# poe.net
KiCad netlist of a schematic drawn in EAGLE
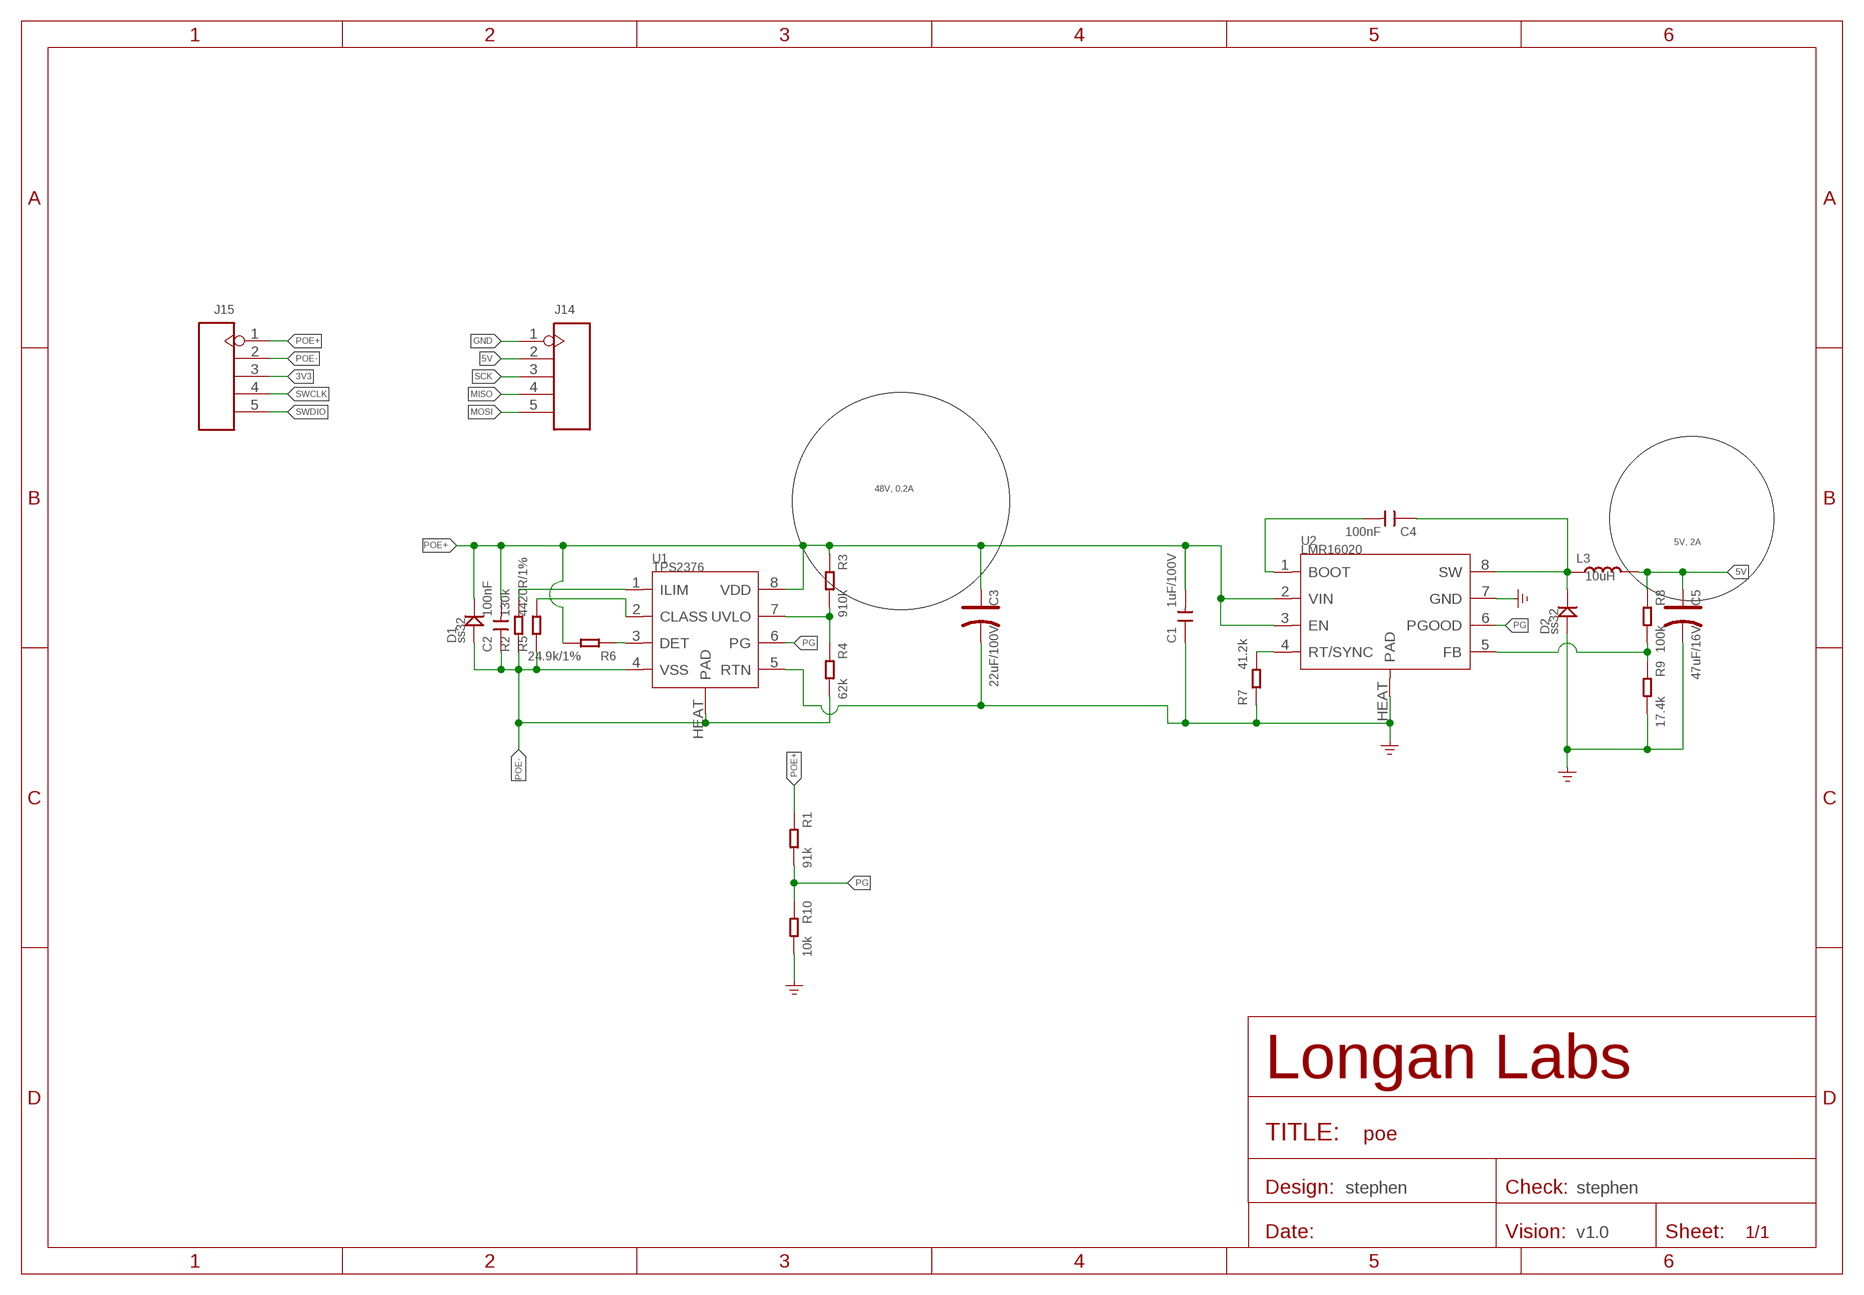
[diagram p0: schematic, sheet 1]

(export (version "E")
  (design (tool "Eeschema 10.0.6"))
  (components
    (comp (ref "C1")
      (value "1uF/100V")
      (footprint "eagle-import:C0805")
      (libsource (lib "eagle-import") (part "CAP-0805"))
    )
    (comp (ref "C2")
      (value "100nF")
      (footprint "eagle-import:C0805")
      (libsource (lib "eagle-import") (part "CAP-0805"))
    )
    (comp (ref "C3")
      (value "22uF/100V")
      (footprint "eagle-import:ELECTRO-SMD-E-7.8MM")
      (libsource (lib "eagle-import") (part "CAP-POLAR-ELECTRO-E"))
    )
    (comp (ref "C4")
      (value "100nF")
      (footprint "eagle-import:C0603")
      (libsource (lib "eagle-import") (part "CAP-0603"))
    )
    (comp (ref "C5")
      (value "47uF/16V")
      (footprint "eagle-import:AVX-B")
      (libsource (lib "eagle-import") (part "CAP-POLAR-AVX-B"))
    )
    (comp (ref "D1")
      (value "ss32")
      (footprint "eagle-import:DO-214AC")
      (libsource (lib "eagle-import") (part "DIODE'SMA'"))
    )
    (comp (ref "D2")
      (value "ss32")
      (footprint "eagle-import:DO-214AC")
      (libsource (lib "eagle-import") (part "DIODE'SMA'"))
    )
    (comp (ref "J14")
      (value "HEADER-5P-2.0")
      (footprint "eagle-import:H5-2.0")
      (libsource (lib "eagle-import") (part "HEADER-5P-2.0"))
    )
    (comp (ref "J15")
      (value "HEADER-5P-2.0")
      (footprint "eagle-import:H5-2.0")
      (libsource (lib "eagle-import") (part "HEADER-5P-2.0"))
    )
    (comp (ref "L3")
      (value "10uH")
      (footprint "eagle-import:INT2-SMD-6.6X7.1X3MM")
      (libsource (lib "eagle-import") (part "INDUCTOR-6.6X7.1"))
    )
    (comp (ref "R1")
      (value "91k")
      (footprint "eagle-import:R0603")
      (libsource (lib "eagle-import") (part "RES-0603"))
    )
    (comp (ref "R2")
      (value "130k")
      (footprint "eagle-import:R0603")
      (libsource (lib "eagle-import") (part "RES-0603"))
    )
    (comp (ref "R3")
      (value "910k")
      (footprint "eagle-import:R0603")
      (libsource (lib "eagle-import") (part "RES-0603"))
    )
    (comp (ref "R4")
      (value "62k")
      (footprint "eagle-import:R0603")
      (libsource (lib "eagle-import") (part "RES-0603"))
    )
    (comp (ref "R5")
      (value "4420R/1%")
      (footprint "eagle-import:R0603")
      (libsource (lib "eagle-import") (part "RES-0603"))
    )
    (comp (ref "R6")
      (value "24.9k/1%")
      (footprint "eagle-import:R0603")
      (libsource (lib "eagle-import") (part "RES-0603"))
    )
    (comp (ref "R7")
      (value "41.2k")
      (footprint "eagle-import:R0603")
      (libsource (lib "eagle-import") (part "RES-0603"))
    )
    (comp (ref "R8")
      (value "100k")
      (footprint "eagle-import:R0603")
      (libsource (lib "eagle-import") (part "RES-0603"))
    )
    (comp (ref "R9")
      (value "17.4k")
      (footprint "eagle-import:R0603")
      (libsource (lib "eagle-import") (part "RES-0603"))
    )
    (comp (ref "R10")
      (value "10k")
      (footprint "eagle-import:R0603")
      (libsource (lib "eagle-import") (part "RES-0603"))
    )
    (comp (ref "U1")
      (value "TPS2376")
      (footprint "eagle-import:SOP8G-1.27-5X3.9MM")
      (libsource (lib "eagle-import") (part "CONTROLLER-TPS2376DDA-H"))
    )
    (comp (ref "U2")
      (value "LMR16020")
      (footprint "eagle-import:SOP8G-1.27-5X3.9MM")
      (libsource (lib "eagle-import") (part "PMIC-LMR16020"))
    )
  )
  (nets
    (net (code "1") (name "3V3") (class "Default")
      (node (ref "J15") (pin "3") (pinfunction "3_3") (pintype "bidirectional"))
    )
    (net (code "2") (name "5V") (class "Default")
      (node (ref "C5") (pin "+") (pinfunction "+_+") (pintype "passive"))
      (node (ref "J14") (pin "2") (pinfunction "2_2") (pintype "bidirectional"))
      (node (ref "L3") (pin "2") (pinfunction "2_2") (pintype "passive"))
      (node (ref "R8") (pin "1") (pinfunction "1_1") (pintype "passive"))
    )
    (net (code "3") (name "GND") (class "Default")
      (node (ref "C1") (pin "1") (pinfunction "1_1") (pintype "passive"))
      (node (ref "C3") (pin "-") (pinfunction "-_-") (pintype "passive"))
      (node (ref "C5") (pin "-") (pinfunction "-_-") (pintype "passive"))
      (node (ref "D2") (pin "1") (pinfunction "+_1") (pintype "passive"))
      (node (ref "J14") (pin "1") (pinfunction "1_1") (pintype "bidirectional"))
      (node (ref "R10") (pin "2") (pinfunction "2_2") (pintype "passive"))
      (node (ref "R7") (pin "1") (pinfunction "1_1") (pintype "passive"))
      (node (ref "R9") (pin "2") (pinfunction "2_2") (pintype "passive"))
      (node (ref "U1") (pin "5") (pinfunction "RTN_5") (pintype "bidirectional"))
      (node (ref "U2") (pin "7") (pinfunction "GND_7") (pintype "bidirectional"))
      (node (ref "U2") (pin "HEAT") (pinfunction "PAD_HEAT") (pintype "bidirectional"))
    )
    (net (code "4") (name "MISO") (class "Default")
      (node (ref "J14") (pin "4") (pinfunction "4_4") (pintype "bidirectional"))
    )
    (net (code "5") (name "MOSI") (class "Default")
      (node (ref "J14") (pin "5") (pinfunction "5_5") (pintype "bidirectional"))
    )
    (net (code "6") (name "Net-(D2--)") (class "Default")
      (node (ref "C4") (pin "1") (pinfunction "1_1") (pintype "passive"))
      (node (ref "D2") (pin "2") (pinfunction "-_2") (pintype "passive"))
      (node (ref "L3") (pin "1") (pinfunction "1_1") (pintype "passive"))
      (node (ref "U2") (pin "8") (pinfunction "SW_8") (pintype "bidirectional"))
    )
    (net (code "7") (name "Net-(U1-CLASS)") (class "Default")
      (node (ref "R5") (pin "2") (pinfunction "2_2") (pintype "passive"))
      (node (ref "U1") (pin "2") (pinfunction "CLASS_2") (pintype "bidirectional"))
    )
    (net (code "8") (name "Net-(U1-DET)") (class "Default")
      (node (ref "R6") (pin "1") (pinfunction "1_1") (pintype "passive"))
      (node (ref "U1") (pin "3") (pinfunction "DET_3") (pintype "bidirectional"))
    )
    (net (code "9") (name "Net-(U1-ILIM)") (class "Default")
      (node (ref "R2") (pin "2") (pinfunction "2_2") (pintype "passive"))
      (node (ref "U1") (pin "1") (pinfunction "ILIM_1") (pintype "bidirectional"))
    )
    (net (code "10") (name "Net-(U1-UVLO)") (class "Default")
      (node (ref "R3") (pin "2") (pinfunction "2_2") (pintype "passive"))
      (node (ref "R4") (pin "1") (pinfunction "1_1") (pintype "passive"))
      (node (ref "U1") (pin "7") (pinfunction "UVLO_7") (pintype "bidirectional"))
    )
    (net (code "11") (name "Net-(U2-BOOT)") (class "Default")
      (node (ref "C4") (pin "2") (pinfunction "2_2") (pintype "passive"))
      (node (ref "U2") (pin "1") (pinfunction "BOOT_1") (pintype "bidirectional"))
    )
    (net (code "12") (name "Net-(U2-FB)") (class "Default")
      (node (ref "R8") (pin "2") (pinfunction "2_2") (pintype "passive"))
      (node (ref "R9") (pin "1") (pinfunction "1_1") (pintype "passive"))
      (node (ref "U2") (pin "5") (pinfunction "FB_5") (pintype "bidirectional"))
    )
    (net (code "13") (name "Net-(U2-RT{slash}SYNC)") (class "Default")
      (node (ref "R7") (pin "2") (pinfunction "2_2") (pintype "passive"))
      (node (ref "U2") (pin "4") (pinfunction "RT/SYNC_4") (pintype "bidirectional"))
    )
    (net (code "14") (name "PG") (class "Default")
      (node (ref "R1") (pin "2") (pinfunction "2_2") (pintype "passive"))
      (node (ref "R10") (pin "1") (pinfunction "1_1") (pintype "passive"))
      (node (ref "U1") (pin "6") (pinfunction "PG_6") (pintype "bidirectional"))
      (node (ref "U2") (pin "6") (pinfunction "PGOOD_6") (pintype "bidirectional"))
    )
    (net (code "15") (name "POE+") (class "Default")
      (node (ref "C1") (pin "2") (pinfunction "2_2") (pintype "passive"))
      (node (ref "C2") (pin "2") (pinfunction "2_2") (pintype "passive"))
      (node (ref "C3") (pin "+") (pinfunction "+_+") (pintype "passive"))
      (node (ref "D1") (pin "2") (pinfunction "-_2") (pintype "passive"))
      (node (ref "J15") (pin "1") (pinfunction "1_1") (pintype "bidirectional"))
      (node (ref "R1") (pin "1") (pinfunction "1_1") (pintype "passive"))
      (node (ref "R3") (pin "1") (pinfunction "1_1") (pintype "passive"))
      (node (ref "R6") (pin "2") (pinfunction "2_2") (pintype "passive"))
      (node (ref "U1") (pin "8") (pinfunction "VDD_8") (pintype "bidirectional"))
      (node (ref "U2") (pin "2") (pinfunction "VIN_2") (pintype "bidirectional"))
      (node (ref "U2") (pin "3") (pinfunction "EN_3") (pintype "bidirectional"))
    )
    (net (code "16") (name "POE-") (class "Default")
      (node (ref "C2") (pin "1") (pinfunction "1_1") (pintype "passive"))
      (node (ref "D1") (pin "1") (pinfunction "+_1") (pintype "passive"))
      (node (ref "J15") (pin "2") (pinfunction "2_2") (pintype "bidirectional"))
      (node (ref "R2") (pin "1") (pinfunction "1_1") (pintype "passive"))
      (node (ref "R4") (pin "2") (pinfunction "2_2") (pintype "passive"))
      (node (ref "R5") (pin "1") (pinfunction "1_1") (pintype "passive"))
      (node (ref "U1") (pin "4") (pinfunction "VSS_4") (pintype "bidirectional"))
      (node (ref "U1") (pin "HEAT") (pinfunction "PAD_HEAT") (pintype "bidirectional"))
    )
    (net (code "17") (name "SCK") (class "Default")
      (node (ref "J14") (pin "3") (pinfunction "3_3") (pintype "bidirectional"))
    )
    (net (code "18") (name "SWCLK") (class "Default")
      (node (ref "J15") (pin "4") (pinfunction "4_4") (pintype "bidirectional"))
    )
    (net (code "19") (name "SWDIO") (class "Default")
      (node (ref "J15") (pin "5") (pinfunction "5_5") (pintype "bidirectional"))
    )
  )
)
